# transducer_array.net
KiCad netlist of a schematic drawn in EAGLE
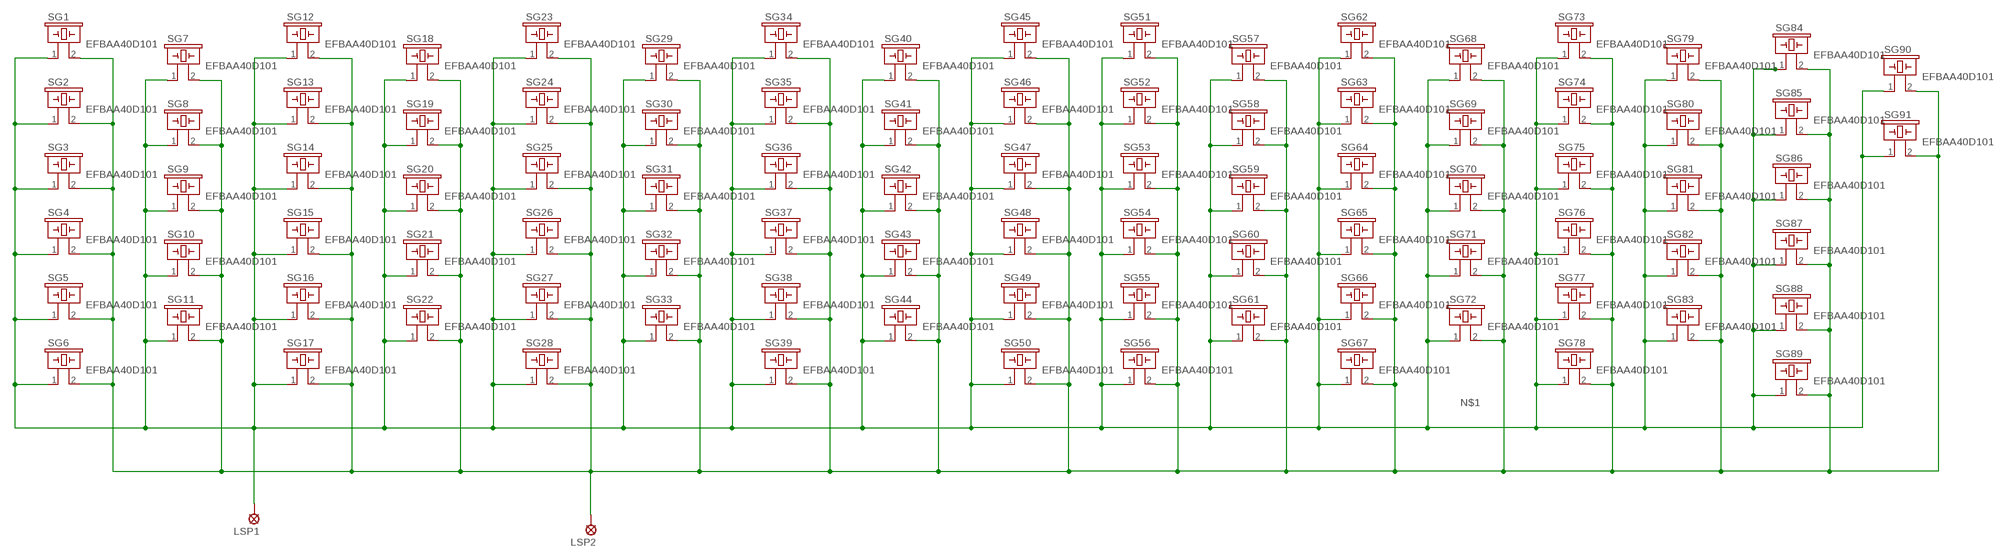
[diagram p0: schematic, sheet 1]

(export (version "E")
  (design (tool "Eeschema 10.0.6"))
  (components
    (comp (ref "LSP1")
      (value "LSP10")
      (footprint "eagle-import:LSP10")
      (libsource (lib "eagle-import") (part "LSP10"))
    )
    (comp (ref "LSP2")
      (value "LSP10")
      (footprint "eagle-import:LSP10")
      (libsource (lib "eagle-import") (part "LSP10"))
    )
    (comp (ref "SG1")
      (value "EFBAA40D101")
      (footprint "eagle-import:EFBAA40D101")
      (libsource (lib "eagle-import") (part "EFB?AA40D101"))
    )
    (comp (ref "SG2")
      (value "EFBAA40D101")
      (footprint "eagle-import:EFBAA40D101")
      (libsource (lib "eagle-import") (part "EFB?AA40D101"))
    )
    (comp (ref "SG3")
      (value "EFBAA40D101")
      (footprint "eagle-import:EFBAA40D101")
      (libsource (lib "eagle-import") (part "EFB?AA40D101"))
    )
    (comp (ref "SG4")
      (value "EFBAA40D101")
      (footprint "eagle-import:EFBAA40D101")
      (libsource (lib "eagle-import") (part "EFB?AA40D101"))
    )
    (comp (ref "SG5")
      (value "EFBAA40D101")
      (footprint "eagle-import:EFBAA40D101")
      (libsource (lib "eagle-import") (part "EFB?AA40D101"))
    )
    (comp (ref "SG6")
      (value "EFBAA40D101")
      (footprint "eagle-import:EFBAA40D101")
      (libsource (lib "eagle-import") (part "EFB?AA40D101"))
    )
    (comp (ref "SG7")
      (value "EFBAA40D101")
      (footprint "eagle-import:EFBAA40D101")
      (libsource (lib "eagle-import") (part "EFB?AA40D101"))
    )
    (comp (ref "SG8")
      (value "EFBAA40D101")
      (footprint "eagle-import:EFBAA40D101")
      (libsource (lib "eagle-import") (part "EFB?AA40D101"))
    )
    (comp (ref "SG9")
      (value "EFBAA40D101")
      (footprint "eagle-import:EFBAA40D101")
      (libsource (lib "eagle-import") (part "EFB?AA40D101"))
    )
    (comp (ref "SG10")
      (value "EFBAA40D101")
      (footprint "eagle-import:EFBAA40D101")
      (libsource (lib "eagle-import") (part "EFB?AA40D101"))
    )
    (comp (ref "SG11")
      (value "EFBAA40D101")
      (footprint "eagle-import:EFBAA40D101")
      (libsource (lib "eagle-import") (part "EFB?AA40D101"))
    )
    (comp (ref "SG12")
      (value "EFBAA40D101")
      (footprint "eagle-import:EFBAA40D101")
      (libsource (lib "eagle-import") (part "EFB?AA40D101"))
    )
    (comp (ref "SG13")
      (value "EFBAA40D101")
      (footprint "eagle-import:EFBAA40D101")
      (libsource (lib "eagle-import") (part "EFB?AA40D101"))
    )
    (comp (ref "SG14")
      (value "EFBAA40D101")
      (footprint "eagle-import:EFBAA40D101")
      (libsource (lib "eagle-import") (part "EFB?AA40D101"))
    )
    (comp (ref "SG15")
      (value "EFBAA40D101")
      (footprint "eagle-import:EFBAA40D101")
      (libsource (lib "eagle-import") (part "EFB?AA40D101"))
    )
    (comp (ref "SG16")
      (value "EFBAA40D101")
      (footprint "eagle-import:EFBAA40D101")
      (libsource (lib "eagle-import") (part "EFB?AA40D101"))
    )
    (comp (ref "SG17")
      (value "EFBAA40D101")
      (footprint "eagle-import:EFBAA40D101")
      (libsource (lib "eagle-import") (part "EFB?AA40D101"))
    )
    (comp (ref "SG18")
      (value "EFBAA40D101")
      (footprint "eagle-import:EFBAA40D101")
      (libsource (lib "eagle-import") (part "EFB?AA40D101"))
    )
    (comp (ref "SG19")
      (value "EFBAA40D101")
      (footprint "eagle-import:EFBAA40D101")
      (libsource (lib "eagle-import") (part "EFB?AA40D101"))
    )
    (comp (ref "SG20")
      (value "EFBAA40D101")
      (footprint "eagle-import:EFBAA40D101")
      (libsource (lib "eagle-import") (part "EFB?AA40D101"))
    )
    (comp (ref "SG21")
      (value "EFBAA40D101")
      (footprint "eagle-import:EFBAA40D101")
      (libsource (lib "eagle-import") (part "EFB?AA40D101"))
    )
    (comp (ref "SG22")
      (value "EFBAA40D101")
      (footprint "eagle-import:EFBAA40D101")
      (libsource (lib "eagle-import") (part "EFB?AA40D101"))
    )
    (comp (ref "SG23")
      (value "EFBAA40D101")
      (footprint "eagle-import:EFBAA40D101")
      (libsource (lib "eagle-import") (part "EFB?AA40D101"))
    )
    (comp (ref "SG24")
      (value "EFBAA40D101")
      (footprint "eagle-import:EFBAA40D101")
      (libsource (lib "eagle-import") (part "EFB?AA40D101"))
    )
    (comp (ref "SG25")
      (value "EFBAA40D101")
      (footprint "eagle-import:EFBAA40D101")
      (libsource (lib "eagle-import") (part "EFB?AA40D101"))
    )
    (comp (ref "SG26")
      (value "EFBAA40D101")
      (footprint "eagle-import:EFBAA40D101")
      (libsource (lib "eagle-import") (part "EFB?AA40D101"))
    )
    (comp (ref "SG27")
      (value "EFBAA40D101")
      (footprint "eagle-import:EFBAA40D101")
      (libsource (lib "eagle-import") (part "EFB?AA40D101"))
    )
    (comp (ref "SG28")
      (value "EFBAA40D101")
      (footprint "eagle-import:EFBAA40D101")
      (libsource (lib "eagle-import") (part "EFB?AA40D101"))
    )
    (comp (ref "SG29")
      (value "EFBAA40D101")
      (footprint "eagle-import:EFBAA40D101")
      (libsource (lib "eagle-import") (part "EFB?AA40D101"))
    )
    (comp (ref "SG30")
      (value "EFBAA40D101")
      (footprint "eagle-import:EFBAA40D101")
      (libsource (lib "eagle-import") (part "EFB?AA40D101"))
    )
    (comp (ref "SG31")
      (value "EFBAA40D101")
      (footprint "eagle-import:EFBAA40D101")
      (libsource (lib "eagle-import") (part "EFB?AA40D101"))
    )
    (comp (ref "SG32")
      (value "EFBAA40D101")
      (footprint "eagle-import:EFBAA40D101")
      (libsource (lib "eagle-import") (part "EFB?AA40D101"))
    )
    (comp (ref "SG33")
      (value "EFBAA40D101")
      (footprint "eagle-import:EFBAA40D101")
      (libsource (lib "eagle-import") (part "EFB?AA40D101"))
    )
    (comp (ref "SG34")
      (value "EFBAA40D101")
      (footprint "eagle-import:EFBAA40D101")
      (libsource (lib "eagle-import") (part "EFB?AA40D101"))
    )
    (comp (ref "SG35")
      (value "EFBAA40D101")
      (footprint "eagle-import:EFBAA40D101")
      (libsource (lib "eagle-import") (part "EFB?AA40D101"))
    )
    (comp (ref "SG36")
      (value "EFBAA40D101")
      (footprint "eagle-import:EFBAA40D101")
      (libsource (lib "eagle-import") (part "EFB?AA40D101"))
    )
    (comp (ref "SG37")
      (value "EFBAA40D101")
      (footprint "eagle-import:EFBAA40D101")
      (libsource (lib "eagle-import") (part "EFB?AA40D101"))
    )
    (comp (ref "SG38")
      (value "EFBAA40D101")
      (footprint "eagle-import:EFBAA40D101")
      (libsource (lib "eagle-import") (part "EFB?AA40D101"))
    )
    (comp (ref "SG39")
      (value "EFBAA40D101")
      (footprint "eagle-import:EFBAA40D101")
      (libsource (lib "eagle-import") (part "EFB?AA40D101"))
    )
    (comp (ref "SG40")
      (value "EFBAA40D101")
      (footprint "eagle-import:EFBAA40D101")
      (libsource (lib "eagle-import") (part "EFB?AA40D101"))
    )
    (comp (ref "SG41")
      (value "EFBAA40D101")
      (footprint "eagle-import:EFBAA40D101")
      (libsource (lib "eagle-import") (part "EFB?AA40D101"))
    )
    (comp (ref "SG42")
      (value "EFBAA40D101")
      (footprint "eagle-import:EFBAA40D101")
      (libsource (lib "eagle-import") (part "EFB?AA40D101"))
    )
    (comp (ref "SG43")
      (value "EFBAA40D101")
      (footprint "eagle-import:EFBAA40D101")
      (libsource (lib "eagle-import") (part "EFB?AA40D101"))
    )
    (comp (ref "SG44")
      (value "EFBAA40D101")
      (footprint "eagle-import:EFBAA40D101")
      (libsource (lib "eagle-import") (part "EFB?AA40D101"))
    )
    (comp (ref "SG45")
      (value "EFBAA40D101")
      (footprint "eagle-import:EFBAA40D101")
      (libsource (lib "eagle-import") (part "EFB?AA40D101"))
    )
    (comp (ref "SG46")
      (value "EFBAA40D101")
      (footprint "eagle-import:EFBAA40D101")
      (libsource (lib "eagle-import") (part "EFB?AA40D101"))
    )
    (comp (ref "SG47")
      (value "EFBAA40D101")
      (footprint "eagle-import:EFBAA40D101")
      (libsource (lib "eagle-import") (part "EFB?AA40D101"))
    )
    (comp (ref "SG48")
      (value "EFBAA40D101")
      (footprint "eagle-import:EFBAA40D101")
      (libsource (lib "eagle-import") (part "EFB?AA40D101"))
    )
    (comp (ref "SG49")
      (value "EFBAA40D101")
      (footprint "eagle-import:EFBAA40D101")
      (libsource (lib "eagle-import") (part "EFB?AA40D101"))
    )
    (comp (ref "SG50")
      (value "EFBAA40D101")
      (footprint "eagle-import:EFBAA40D101")
      (libsource (lib "eagle-import") (part "EFB?AA40D101"))
    )
    (comp (ref "SG51")
      (value "EFBAA40D101")
      (footprint "eagle-import:EFBAA40D101")
      (libsource (lib "eagle-import") (part "EFB?AA40D101"))
    )
    (comp (ref "SG52")
      (value "EFBAA40D101")
      (footprint "eagle-import:EFBAA40D101")
      (libsource (lib "eagle-import") (part "EFB?AA40D101"))
    )
    (comp (ref "SG53")
      (value "EFBAA40D101")
      (footprint "eagle-import:EFBAA40D101")
      (libsource (lib "eagle-import") (part "EFB?AA40D101"))
    )
    (comp (ref "SG54")
      (value "EFBAA40D101")
      (footprint "eagle-import:EFBAA40D101")
      (libsource (lib "eagle-import") (part "EFB?AA40D101"))
    )
    (comp (ref "SG55")
      (value "EFBAA40D101")
      (footprint "eagle-import:EFBAA40D101")
      (libsource (lib "eagle-import") (part "EFB?AA40D101"))
    )
    (comp (ref "SG56")
      (value "EFBAA40D101")
      (footprint "eagle-import:EFBAA40D101")
      (libsource (lib "eagle-import") (part "EFB?AA40D101"))
    )
    (comp (ref "SG57")
      (value "EFBAA40D101")
      (footprint "eagle-import:EFBAA40D101")
      (libsource (lib "eagle-import") (part "EFB?AA40D101"))
    )
    (comp (ref "SG58")
      (value "EFBAA40D101")
      (footprint "eagle-import:EFBAA40D101")
      (libsource (lib "eagle-import") (part "EFB?AA40D101"))
    )
    (comp (ref "SG59")
      (value "EFBAA40D101")
      (footprint "eagle-import:EFBAA40D101")
      (libsource (lib "eagle-import") (part "EFB?AA40D101"))
    )
    (comp (ref "SG60")
      (value "EFBAA40D101")
      (footprint "eagle-import:EFBAA40D101")
      (libsource (lib "eagle-import") (part "EFB?AA40D101"))
    )
    (comp (ref "SG61")
      (value "EFBAA40D101")
      (footprint "eagle-import:EFBAA40D101")
      (libsource (lib "eagle-import") (part "EFB?AA40D101"))
    )
    (comp (ref "SG62")
      (value "EFBAA40D101")
      (footprint "eagle-import:EFBAA40D101")
      (libsource (lib "eagle-import") (part "EFB?AA40D101"))
    )
    (comp (ref "SG63")
      (value "EFBAA40D101")
      (footprint "eagle-import:EFBAA40D101")
      (libsource (lib "eagle-import") (part "EFB?AA40D101"))
    )
    (comp (ref "SG64")
      (value "EFBAA40D101")
      (footprint "eagle-import:EFBAA40D101")
      (libsource (lib "eagle-import") (part "EFB?AA40D101"))
    )
    (comp (ref "SG65")
      (value "EFBAA40D101")
      (footprint "eagle-import:EFBAA40D101")
      (libsource (lib "eagle-import") (part "EFB?AA40D101"))
    )
    (comp (ref "SG66")
      (value "EFBAA40D101")
      (footprint "eagle-import:EFBAA40D101")
      (libsource (lib "eagle-import") (part "EFB?AA40D101"))
    )
    (comp (ref "SG67")
      (value "EFBAA40D101")
      (footprint "eagle-import:EFBAA40D101")
      (libsource (lib "eagle-import") (part "EFB?AA40D101"))
    )
    (comp (ref "SG68")
      (value "EFBAA40D101")
      (footprint "eagle-import:EFBAA40D101")
      (libsource (lib "eagle-import") (part "EFB?AA40D101"))
    )
    (comp (ref "SG69")
      (value "EFBAA40D101")
      (footprint "eagle-import:EFBAA40D101")
      (libsource (lib "eagle-import") (part "EFB?AA40D101"))
    )
    (comp (ref "SG70")
      (value "EFBAA40D101")
      (footprint "eagle-import:EFBAA40D101")
      (libsource (lib "eagle-import") (part "EFB?AA40D101"))
    )
    (comp (ref "SG71")
      (value "EFBAA40D101")
      (footprint "eagle-import:EFBAA40D101")
      (libsource (lib "eagle-import") (part "EFB?AA40D101"))
    )
    (comp (ref "SG72")
      (value "EFBAA40D101")
      (footprint "eagle-import:EFBAA40D101")
      (libsource (lib "eagle-import") (part "EFB?AA40D101"))
    )
    (comp (ref "SG73")
      (value "EFBAA40D101")
      (footprint "eagle-import:EFBAA40D101")
      (libsource (lib "eagle-import") (part "EFB?AA40D101"))
    )
    (comp (ref "SG74")
      (value "EFBAA40D101")
      (footprint "eagle-import:EFBAA40D101")
      (libsource (lib "eagle-import") (part "EFB?AA40D101"))
    )
    (comp (ref "SG75")
      (value "EFBAA40D101")
      (footprint "eagle-import:EFBAA40D101")
      (libsource (lib "eagle-import") (part "EFB?AA40D101"))
    )
    (comp (ref "SG76")
      (value "EFBAA40D101")
      (footprint "eagle-import:EFBAA40D101")
      (libsource (lib "eagle-import") (part "EFB?AA40D101"))
    )
    (comp (ref "SG77")
      (value "EFBAA40D101")
      (footprint "eagle-import:EFBAA40D101")
      (libsource (lib "eagle-import") (part "EFB?AA40D101"))
    )
    (comp (ref "SG78")
      (value "EFBAA40D101")
      (footprint "eagle-import:EFBAA40D101")
      (libsource (lib "eagle-import") (part "EFB?AA40D101"))
    )
    (comp (ref "SG79")
      (value "EFBAA40D101")
      (footprint "eagle-import:EFBAA40D101")
      (libsource (lib "eagle-import") (part "EFB?AA40D101"))
    )
    (comp (ref "SG80")
      (value "EFBAA40D101")
      (footprint "eagle-import:EFBAA40D101")
      (libsource (lib "eagle-import") (part "EFB?AA40D101"))
    )
    (comp (ref "SG81")
      (value "EFBAA40D101")
      (footprint "eagle-import:EFBAA40D101")
      (libsource (lib "eagle-import") (part "EFB?AA40D101"))
    )
    (comp (ref "SG82")
      (value "EFBAA40D101")
      (footprint "eagle-import:EFBAA40D101")
      (libsource (lib "eagle-import") (part "EFB?AA40D101"))
    )
    (comp (ref "SG83")
      (value "EFBAA40D101")
      (footprint "eagle-import:EFBAA40D101")
      (libsource (lib "eagle-import") (part "EFB?AA40D101"))
    )
    (comp (ref "SG84")
      (value "EFBAA40D101")
      (footprint "eagle-import:EFBAA40D101")
      (libsource (lib "eagle-import") (part "EFB?AA40D101"))
    )
    (comp (ref "SG85")
      (value "EFBAA40D101")
      (footprint "eagle-import:EFBAA40D101")
      (libsource (lib "eagle-import") (part "EFB?AA40D101"))
    )
    (comp (ref "SG86")
      (value "EFBAA40D101")
      (footprint "eagle-import:EFBAA40D101")
      (libsource (lib "eagle-import") (part "EFB?AA40D101"))
    )
    (comp (ref "SG87")
      (value "EFBAA40D101")
      (footprint "eagle-import:EFBAA40D101")
      (libsource (lib "eagle-import") (part "EFB?AA40D101"))
    )
    (comp (ref "SG88")
      (value "EFBAA40D101")
      (footprint "eagle-import:EFBAA40D101")
      (libsource (lib "eagle-import") (part "EFB?AA40D101"))
    )
    (comp (ref "SG89")
      (value "EFBAA40D101")
      (footprint "eagle-import:EFBAA40D101")
      (libsource (lib "eagle-import") (part "EFB?AA40D101"))
    )
    (comp (ref "SG90")
      (value "EFBAA40D101")
      (footprint "eagle-import:EFBAA40D101")
      (libsource (lib "eagle-import") (part "EFB?AA40D101"))
    )
    (comp (ref "SG91")
      (value "EFBAA40D101")
      (footprint "eagle-import:EFBAA40D101")
      (libsource (lib "eagle-import") (part "EFB?AA40D101"))
    )
  )
  (nets
    (net (code "1") (name "/N$1") (class "Default")
      (node (ref "LSP1") (pin "MP") (pinfunction "MP_MP") (pintype "passive"))
      (node (ref "SG1") (pin "1") (pinfunction "1_1") (pintype "passive"))
      (node (ref "SG10") (pin "1") (pinfunction "1_1") (pintype "passive"))
      (node (ref "SG11") (pin "1") (pinfunction "1_1") (pintype "passive"))
      (node (ref "SG12") (pin "1") (pinfunction "1_1") (pintype "passive"))
      (node (ref "SG13") (pin "1") (pinfunction "1_1") (pintype "passive"))
      (node (ref "SG14") (pin "1") (pinfunction "1_1") (pintype "passive"))
      (node (ref "SG15") (pin "1") (pinfunction "1_1") (pintype "passive"))
      (node (ref "SG16") (pin "1") (pinfunction "1_1") (pintype "passive"))
      (node (ref "SG17") (pin "1") (pinfunction "1_1") (pintype "passive"))
      (node (ref "SG18") (pin "1") (pinfunction "1_1") (pintype "passive"))
      (node (ref "SG19") (pin "1") (pinfunction "1_1") (pintype "passive"))
      (node (ref "SG2") (pin "1") (pinfunction "1_1") (pintype "passive"))
      (node (ref "SG20") (pin "1") (pinfunction "1_1") (pintype "passive"))
      (node (ref "SG21") (pin "1") (pinfunction "1_1") (pintype "passive"))
      (node (ref "SG22") (pin "1") (pinfunction "1_1") (pintype "passive"))
      (node (ref "SG23") (pin "1") (pinfunction "1_1") (pintype "passive"))
      (node (ref "SG24") (pin "1") (pinfunction "1_1") (pintype "passive"))
      (node (ref "SG25") (pin "1") (pinfunction "1_1") (pintype "passive"))
      (node (ref "SG26") (pin "1") (pinfunction "1_1") (pintype "passive"))
      (node (ref "SG27") (pin "1") (pinfunction "1_1") (pintype "passive"))
      (node (ref "SG28") (pin "1") (pinfunction "1_1") (pintype "passive"))
      (node (ref "SG29") (pin "1") (pinfunction "1_1") (pintype "passive"))
      (node (ref "SG3") (pin "1") (pinfunction "1_1") (pintype "passive"))
      (node (ref "SG30") (pin "1") (pinfunction "1_1") (pintype "passive"))
      (node (ref "SG31") (pin "1") (pinfunction "1_1") (pintype "passive"))
      (node (ref "SG32") (pin "1") (pinfunction "1_1") (pintype "passive"))
      (node (ref "SG33") (pin "1") (pinfunction "1_1") (pintype "passive"))
      (node (ref "SG34") (pin "1") (pinfunction "1_1") (pintype "passive"))
      (node (ref "SG35") (pin "1") (pinfunction "1_1") (pintype "passive"))
      (node (ref "SG36") (pin "1") (pinfunction "1_1") (pintype "passive"))
      (node (ref "SG37") (pin "1") (pinfunction "1_1") (pintype "passive"))
      (node (ref "SG38") (pin "1") (pinfunction "1_1") (pintype "passive"))
      (node (ref "SG39") (pin "1") (pinfunction "1_1") (pintype "passive"))
      (node (ref "SG4") (pin "1") (pinfunction "1_1") (pintype "passive"))
      (node (ref "SG40") (pin "1") (pinfunction "1_1") (pintype "passive"))
      (node (ref "SG41") (pin "1") (pinfunction "1_1") (pintype "passive"))
      (node (ref "SG42") (pin "1") (pinfunction "1_1") (pintype "passive"))
      (node (ref "SG43") (pin "1") (pinfunction "1_1") (pintype "passive"))
      (node (ref "SG44") (pin "1") (pinfunction "1_1") (pintype "passive"))
      (node (ref "SG45") (pin "1") (pinfunction "1_1") (pintype "passive"))
      (node (ref "SG46") (pin "1") (pinfunction "1_1") (pintype "passive"))
      (node (ref "SG47") (pin "1") (pinfunction "1_1") (pintype "passive"))
      (node (ref "SG48") (pin "1") (pinfunction "1_1") (pintype "passive"))
      (node (ref "SG49") (pin "1") (pinfunction "1_1") (pintype "passive"))
      (node (ref "SG5") (pin "1") (pinfunction "1_1") (pintype "passive"))
      (node (ref "SG50") (pin "1") (pinfunction "1_1") (pintype "passive"))
      (node (ref "SG51") (pin "1") (pinfunction "1_1") (pintype "passive"))
      (node (ref "SG52") (pin "1") (pinfunction "1_1") (pintype "passive"))
      (node (ref "SG53") (pin "1") (pinfunction "1_1") (pintype "passive"))
      (node (ref "SG54") (pin "1") (pinfunction "1_1") (pintype "passive"))
      (node (ref "SG55") (pin "1") (pinfunction "1_1") (pintype "passive"))
      (node (ref "SG56") (pin "1") (pinfunction "1_1") (pintype "passive"))
      (node (ref "SG57") (pin "1") (pinfunction "1_1") (pintype "passive"))
      (node (ref "SG58") (pin "1") (pinfunction "1_1") (pintype "passive"))
      (node (ref "SG59") (pin "1") (pinfunction "1_1") (pintype "passive"))
      (node (ref "SG6") (pin "1") (pinfunction "1_1") (pintype "passive"))
      (node (ref "SG60") (pin "1") (pinfunction "1_1") (pintype "passive"))
      (node (ref "SG61") (pin "1") (pinfunction "1_1") (pintype "passive"))
      (node (ref "SG62") (pin "1") (pinfunction "1_1") (pintype "passive"))
      (node (ref "SG63") (pin "1") (pinfunction "1_1") (pintype "passive"))
      (node (ref "SG64") (pin "1") (pinfunction "1_1") (pintype "passive"))
      (node (ref "SG65") (pin "1") (pinfunction "1_1") (pintype "passive"))
      (node (ref "SG66") (pin "1") (pinfunction "1_1") (pintype "passive"))
      (node (ref "SG67") (pin "1") (pinfunction "1_1") (pintype "passive"))
      (node (ref "SG68") (pin "1") (pinfunction "1_1") (pintype "passive"))
      (node (ref "SG69") (pin "1") (pinfunction "1_1") (pintype "passive"))
      (node (ref "SG7") (pin "1") (pinfunction "1_1") (pintype "passive"))
      (node (ref "SG70") (pin "1") (pinfunction "1_1") (pintype "passive"))
      (node (ref "SG71") (pin "1") (pinfunction "1_1") (pintype "passive"))
      (node (ref "SG72") (pin "1") (pinfunction "1_1") (pintype "passive"))
      (node (ref "SG73") (pin "1") (pinfunction "1_1") (pintype "passive"))
      (node (ref "SG74") (pin "1") (pinfunction "1_1") (pintype "passive"))
      (node (ref "SG75") (pin "1") (pinfunction "1_1") (pintype "passive"))
      (node (ref "SG76") (pin "1") (pinfunction "1_1") (pintype "passive"))
      (node (ref "SG77") (pin "1") (pinfunction "1_1") (pintype "passive"))
      (node (ref "SG78") (pin "1") (pinfunction "1_1") (pintype "passive"))
      (node (ref "SG79") (pin "1") (pinfunction "1_1") (pintype "passive"))
      (node (ref "SG8") (pin "1") (pinfunction "1_1") (pintype "passive"))
      (node (ref "SG80") (pin "1") (pinfunction "1_1") (pintype "passive"))
      (node (ref "SG81") (pin "1") (pinfunction "1_1") (pintype "passive"))
      (node (ref "SG82") (pin "1") (pinfunction "1_1") (pintype "passive"))
      (node (ref "SG83") (pin "1") (pinfunction "1_1") (pintype "passive"))
      (node (ref "SG84") (pin "1") (pinfunction "1_1") (pintype "passive"))
      (node (ref "SG85") (pin "1") (pinfunction "1_1") (pintype "passive"))
      (node (ref "SG86") (pin "1") (pinfunction "1_1") (pintype "passive"))
      (node (ref "SG87") (pin "1") (pinfunction "1_1") (pintype "passive"))
      (node (ref "SG88") (pin "1") (pinfunction "1_1") (pintype "passive"))
      (node (ref "SG89") (pin "1") (pinfunction "1_1") (pintype "passive"))
      (node (ref "SG9") (pin "1") (pinfunction "1_1") (pintype "passive"))
      (node (ref "SG90") (pin "1") (pinfunction "1_1") (pintype "passive"))
      (node (ref "SG91") (pin "1") (pinfunction "1_1") (pintype "passive"))
    )
    (net (code "2") (name "Net-(LSP2-PadMP)") (class "Default")
      (node (ref "LSP2") (pin "MP") (pinfunction "MP_MP") (pintype "passive"))
      (node (ref "SG1") (pin "2") (pinfunction "2_2") (pintype "passive"))
      (node (ref "SG10") (pin "2") (pinfunction "2_2") (pintype "passive"))
      (node (ref "SG11") (pin "2") (pinfunction "2_2") (pintype "passive"))
      (node (ref "SG12") (pin "2") (pinfunction "2_2") (pintype "passive"))
      (node (ref "SG13") (pin "2") (pinfunction "2_2") (pintype "passive"))
      (node (ref "SG14") (pin "2") (pinfunction "2_2") (pintype "passive"))
      (node (ref "SG15") (pin "2") (pinfunction "2_2") (pintype "passive"))
      (node (ref "SG16") (pin "2") (pinfunction "2_2") (pintype "passive"))
      (node (ref "SG17") (pin "2") (pinfunction "2_2") (pintype "passive"))
      (node (ref "SG18") (pin "2") (pinfunction "2_2") (pintype "passive"))
      (node (ref "SG19") (pin "2") (pinfunction "2_2") (pintype "passive"))
      (node (ref "SG2") (pin "2") (pinfunction "2_2") (pintype "passive"))
      (node (ref "SG20") (pin "2") (pinfunction "2_2") (pintype "passive"))
      (node (ref "SG21") (pin "2") (pinfunction "2_2") (pintype "passive"))
      (node (ref "SG22") (pin "2") (pinfunction "2_2") (pintype "passive"))
      (node (ref "SG23") (pin "2") (pinfunction "2_2") (pintype "passive"))
      (node (ref "SG24") (pin "2") (pinfunction "2_2") (pintype "passive"))
      (node (ref "SG25") (pin "2") (pinfunction "2_2") (pintype "passive"))
      (node (ref "SG26") (pin "2") (pinfunction "2_2") (pintype "passive"))
      (node (ref "SG27") (pin "2") (pinfunction "2_2") (pintype "passive"))
      (node (ref "SG28") (pin "2") (pinfunction "2_2") (pintype "passive"))
      (node (ref "SG29") (pin "2") (pinfunction "2_2") (pintype "passive"))
      (node (ref "SG3") (pin "2") (pinfunction "2_2") (pintype "passive"))
      (node (ref "SG30") (pin "2") (pinfunction "2_2") (pintype "passive"))
      (node (ref "SG31") (pin "2") (pinfunction "2_2") (pintype "passive"))
      (node (ref "SG32") (pin "2") (pinfunction "2_2") (pintype "passive"))
      (node (ref "SG33") (pin "2") (pinfunction "2_2") (pintype "passive"))
      (node (ref "SG34") (pin "2") (pinfunction "2_2") (pintype "passive"))
      (node (ref "SG35") (pin "2") (pinfunction "2_2") (pintype "passive"))
      (node (ref "SG36") (pin "2") (pinfunction "2_2") (pintype "passive"))
      (node (ref "SG37") (pin "2") (pinfunction "2_2") (pintype "passive"))
      (node (ref "SG38") (pin "2") (pinfunction "2_2") (pintype "passive"))
      (node (ref "SG39") (pin "2") (pinfunction "2_2") (pintype "passive"))
      (node (ref "SG4") (pin "2") (pinfunction "2_2") (pintype "passive"))
      (node (ref "SG40") (pin "2") (pinfunction "2_2") (pintype "passive"))
      (node (ref "SG41") (pin "2") (pinfunction "2_2") (pintype "passive"))
      (node (ref "SG42") (pin "2") (pinfunction "2_2") (pintype "passive"))
      (node (ref "SG43") (pin "2") (pinfunction "2_2") (pintype "passive"))
      (node (ref "SG44") (pin "2") (pinfunction "2_2") (pintype "passive"))
      (node (ref "SG45") (pin "2") (pinfunction "2_2") (pintype "passive"))
      (node (ref "SG46") (pin "2") (pinfunction "2_2") (pintype "passive"))
      (node (ref "SG47") (pin "2") (pinfunction "2_2") (pintype "passive"))
      (node (ref "SG48") (pin "2") (pinfunction "2_2") (pintype "passive"))
      (node (ref "SG49") (pin "2") (pinfunction "2_2") (pintype "passive"))
      (node (ref "SG5") (pin "2") (pinfunction "2_2") (pintype "passive"))
      (node (ref "SG50") (pin "2") (pinfunction "2_2") (pintype "passive"))
      (node (ref "SG51") (pin "2") (pinfunction "2_2") (pintype "passive"))
      (node (ref "SG52") (pin "2") (pinfunction "2_2") (pintype "passive"))
      (node (ref "SG53") (pin "2") (pinfunction "2_2") (pintype "passive"))
      (node (ref "SG54") (pin "2") (pinfunction "2_2") (pintype "passive"))
      (node (ref "SG55") (pin "2") (pinfunction "2_2") (pintype "passive"))
      (node (ref "SG56") (pin "2") (pinfunction "2_2") (pintype "passive"))
      (node (ref "SG57") (pin "2") (pinfunction "2_2") (pintype "passive"))
      (node (ref "SG58") (pin "2") (pinfunction "2_2") (pintype "passive"))
      (node (ref "SG59") (pin "2") (pinfunction "2_2") (pintype "passive"))
      (node (ref "SG6") (pin "2") (pinfunction "2_2") (pintype "passive"))
      (node (ref "SG60") (pin "2") (pinfunction "2_2") (pintype "passive"))
      (node (ref "SG61") (pin "2") (pinfunction "2_2") (pintype "passive"))
      (node (ref "SG62") (pin "2") (pinfunction "2_2") (pintype "passive"))
      (node (ref "SG63") (pin "2") (pinfunction "2_2") (pintype "passive"))
      (node (ref "SG64") (pin "2") (pinfunction "2_2") (pintype "passive"))
      (node (ref "SG65") (pin "2") (pinfunction "2_2") (pintype "passive"))
      (node (ref "SG66") (pin "2") (pinfunction "2_2") (pintype "passive"))
      (node (ref "SG67") (pin "2") (pinfunction "2_2") (pintype "passive"))
      (node (ref "SG68") (pin "2") (pinfunction "2_2") (pintype "passive"))
      (node (ref "SG69") (pin "2") (pinfunction "2_2") (pintype "passive"))
      (node (ref "SG7") (pin "2") (pinfunction "2_2") (pintype "passive"))
      (node (ref "SG70") (pin "2") (pinfunction "2_2") (pintype "passive"))
      (node (ref "SG71") (pin "2") (pinfunction "2_2") (pintype "passive"))
      (node (ref "SG72") (pin "2") (pinfunction "2_2") (pintype "passive"))
      (node (ref "SG73") (pin "2") (pinfunction "2_2") (pintype "passive"))
      (node (ref "SG74") (pin "2") (pinfunction "2_2") (pintype "passive"))
      (node (ref "SG75") (pin "2") (pinfunction "2_2") (pintype "passive"))
      (node (ref "SG76") (pin "2") (pinfunction "2_2") (pintype "passive"))
      (node (ref "SG77") (pin "2") (pinfunction "2_2") (pintype "passive"))
      (node (ref "SG78") (pin "2") (pinfunction "2_2") (pintype "passive"))
      (node (ref "SG79") (pin "2") (pinfunction "2_2") (pintype "passive"))
      (node (ref "SG8") (pin "2") (pinfunction "2_2") (pintype "passive"))
      (node (ref "SG80") (pin "2") (pinfunction "2_2") (pintype "passive"))
      (node (ref "SG81") (pin "2") (pinfunction "2_2") (pintype "passive"))
      (node (ref "SG82") (pin "2") (pinfunction "2_2") (pintype "passive"))
      (node (ref "SG83") (pin "2") (pinfunction "2_2") (pintype "passive"))
      (node (ref "SG84") (pin "2") (pinfunction "2_2") (pintype "passive"))
      (node (ref "SG85") (pin "2") (pinfunction "2_2") (pintype "passive"))
      (node (ref "SG86") (pin "2") (pinfunction "2_2") (pintype "passive"))
      (node (ref "SG87") (pin "2") (pinfunction "2_2") (pintype "passive"))
      (node (ref "SG88") (pin "2") (pinfunction "2_2") (pintype "passive"))
      (node (ref "SG89") (pin "2") (pinfunction "2_2") (pintype "passive"))
      (node (ref "SG9") (pin "2") (pinfunction "2_2") (pintype "passive"))
      (node (ref "SG90") (pin "2") (pinfunction "2_2") (pintype "passive"))
      (node (ref "SG91") (pin "2") (pinfunction "2_2") (pintype "passive"))
    )
  )
)
